# UVLO_MODULE_TOP.net
KiCad netlist of a schematic drawn in Altium Designer
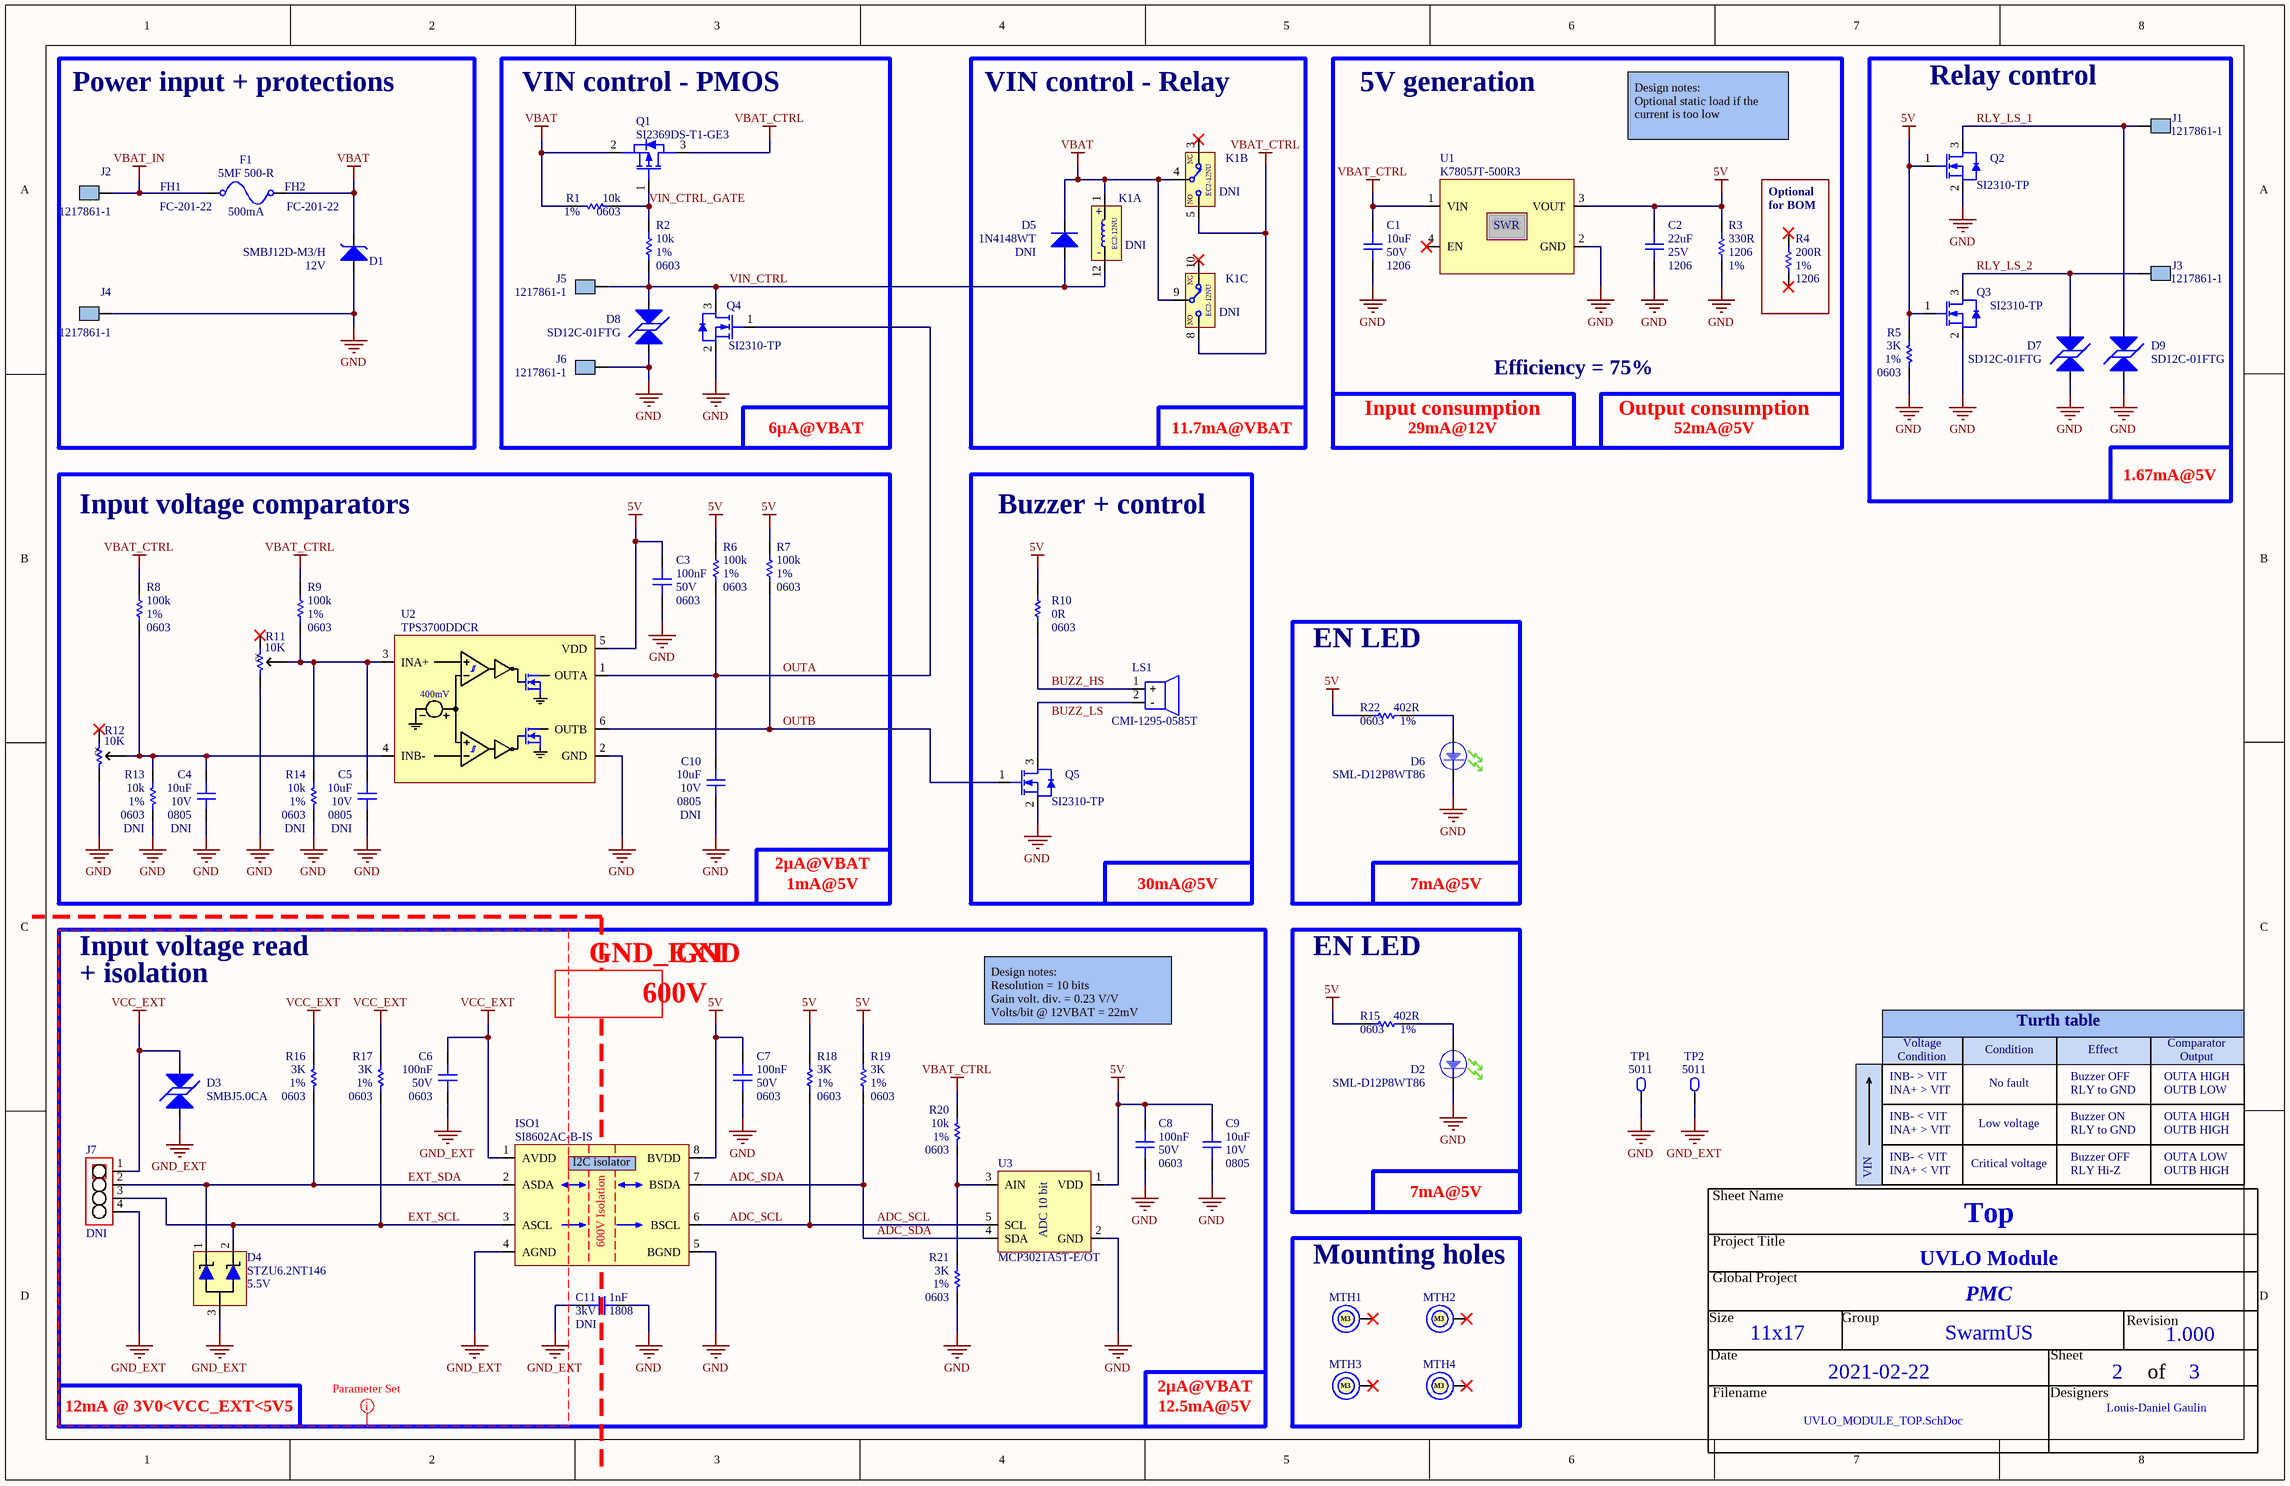
[diagram p0: UVLO_MODULE_TOP.SchDoc]

(export (version "E")
  (design (tool "Eeschema 10.0.6"))
  (components
    (comp (ref "C1")
      (value "10uF")
      (footprint "CAP_CER_1206")
      (description "CAP - CER 10UF 10% 50V X5R - 1206")
      (fields
        (field (name "TOLERANCE") "10%")
        (field (name "PACKAGE") "1206")
        (field (name "VOLTAGE RATING") "50V")
        (field (name "Comment") "GRT31CR61H106KE01L")
        (field (name "CREATEDBY/DATE") "Nicolas Roy - 2018/12/19")
        (field (name "VERIFIEDBY") "Nicolas V. (2019-01-22)")
      )
      (libsource (lib "GRAMS_MASTER_LIB") (part "CAP_CER_GRT31CR61H106KE01L"))
    )
    (comp (ref "C2")
      (value "22uF")
      (footprint "CAP_CER_1206")
      (description "CAP - CER 22uF 10% 25V X5R - 1206")
      (fields
        (field (name "TOLERANCE") "10%")
        (field (name "PACKAGE") "1206")
        (field (name "VOLTAGE RATING") "25V")
        (field (name "Comment") "CL31A226KAHNNNE")
        (field (name "CREATEDBY/DATE") "Philippe Arsenault/21 Janvier 2020")
        (field (name "VERIFIEDBY") "C.Paulin - 28/01/2020")
      )
      (libsource (lib "GRAMS_MASTER_LIB") (part "CAP_CER_CL31A226KAHNNNE"))
    )
    (comp (ref "C3")
      (value "100nF")
      (footprint "CAP_CER_0603")
      (description "CAP - CER 100nF 50V X7R - 0603")
      (fields
        (field (name "TOLERANCE") "10%")
        (field (name "PACKAGE") "0603")
        (field (name "VOLTAGE RATING") "50V")
        (field (name "Comment") "CC0603KRX7R9BB104")
        (field (name "CREATEDBY/DATE") "Louis-Daniel Gaulin / 25-02-2021")
        (field (name "VERIFIEDBY") "Hubert Dube - 26/02/2021")
      )
      (libsource (lib "SWARMUS_LIB") (part "CAP_CER_CC0603KRX7R9BB104"))
    )
    (comp (ref "C4")
      (value "10uF")
      (footprint "CAP_CER_0805")
      (description "CAP - CER 10UF 10% 10V X5R - 0805")
      (fields
        (field (name "TOLERANCE") "10%")
        (field (name "ASSEMBLY NOTE") "DNI")
        (field (name "PACKAGE") "0805")
        (field (name "VOLTAGE RATING") "10V")
        (field (name "Comment") "LMK212BJ106KG-T")
        (field (name "CREATEDBY/DATE") "Caroline Paulin / 25 juillet 2018")
        (field (name "VERIFIEDBY") "Nicolas V. (2019-01-22)")
      )
      (libsource (lib "GRAMS_MASTER_LIB") (part "CAP_CER_LMK212BJ106KG-T"))
    )
    (comp (ref "C5")
      (value "10uF")
      (footprint "CAP_CER_0805")
      (description "CAP - CER 10UF 10% 10V X5R - 0805")
      (fields
        (field (name "TOLERANCE") "10%")
        (field (name "ASSEMBLY NOTE") "DNI")
        (field (name "PACKAGE") "0805")
        (field (name "VOLTAGE RATING") "10V")
        (field (name "Comment") "LMK212BJ106KG-T")
        (field (name "CREATEDBY/DATE") "Caroline Paulin / 25 juillet 2018")
        (field (name "VERIFIEDBY") "Nicolas V. (2019-01-22)")
      )
      (libsource (lib "GRAMS_MASTER_LIB") (part "CAP_CER_LMK212BJ106KG-T"))
    )
    (comp (ref "C6")
      (value "100nF")
      (footprint "CAP_CER_0603")
      (description "CAP - CER 100nF 50V X7R - 0603")
      (fields
        (field (name "TOLERANCE") "10%")
        (field (name "PACKAGE") "0603")
        (field (name "VOLTAGE RATING") "50V")
        (field (name "Comment") "CC0603KRX7R9BB104")
        (field (name "CREATEDBY/DATE") "Louis-Daniel Gaulin / 25-02-2021")
        (field (name "VERIFIEDBY") "Hubert Dube - 26/02/2021")
      )
      (libsource (lib "SWARMUS_LIB") (part "CAP_CER_CC0603KRX7R9BB104"))
    )
    (comp (ref "C7")
      (value "100nF")
      (footprint "CAP_CER_0603")
      (description "CAP - CER 100nF 50V X7R - 0603")
      (fields
        (field (name "TOLERANCE") "10%")
        (field (name "PACKAGE") "0603")
        (field (name "VOLTAGE RATING") "50V")
        (field (name "Comment") "CC0603KRX7R9BB104")
        (field (name "CREATEDBY/DATE") "Louis-Daniel Gaulin / 25-02-2021")
        (field (name "VERIFIEDBY") "Hubert Dube - 26/02/2021")
      )
      (libsource (lib "SWARMUS_LIB") (part "CAP_CER_CC0603KRX7R9BB104"))
    )
    (comp (ref "C8")
      (value "100nF")
      (footprint "CAP_CER_0603")
      (description "CAP - CER 100nF 50V X7R - 0603")
      (fields
        (field (name "TOLERANCE") "10%")
        (field (name "PACKAGE") "0603")
        (field (name "VOLTAGE RATING") "50V")
        (field (name "Comment") "CC0603KRX7R9BB104")
        (field (name "CREATEDBY/DATE") "Louis-Daniel Gaulin / 25-02-2021")
        (field (name "VERIFIEDBY") "Hubert Dube - 26/02/2021")
      )
      (libsource (lib "SWARMUS_LIB") (part "CAP_CER_CC0603KRX7R9BB104"))
    )
    (comp (ref "C9")
      (value "10uF")
      (footprint "CAP_CER_0805")
      (description "CAP - CER 10UF 10% 10V X5R - 0805")
      (fields
        (field (name "TOLERANCE") "10%")
        (field (name "PACKAGE") "0805")
        (field (name "VOLTAGE RATING") "10V")
        (field (name "Comment") "LMK212BJ106KG-T")
        (field (name "CREATEDBY/DATE") "Caroline Paulin / 25 juillet 2018")
        (field (name "VERIFIEDBY") "Nicolas V. (2019-01-22)")
      )
      (libsource (lib "GRAMS_MASTER_LIB") (part "CAP_CER_LMK212BJ106KG-T"))
    )
    (comp (ref "C10")
      (value "10uF")
      (footprint "CAP_CER_0805")
      (description "CAP - CER 10UF 10% 10V X5R - 0805")
      (fields
        (field (name "TOLERANCE") "10%")
        (field (name "ASSEMBLY NOTE") "DNI")
        (field (name "PACKAGE") "0805")
        (field (name "VOLTAGE RATING") "10V")
        (field (name "Comment") "LMK212BJ106KG-T")
        (field (name "CREATEDBY/DATE") "Caroline Paulin / 25 juillet 2018")
        (field (name "VERIFIEDBY") "Nicolas V. (2019-01-22)")
      )
      (libsource (lib "GRAMS_MASTER_LIB") (part "CAP_CER_LMK212BJ106KG-T"))
    )
    (comp (ref "C11")
      (value "1nF")
      (footprint "CAP_CER_1808")
      (description "CAP - CER 1nF 10% 3kV X7R - 1808")
      (fields
        (field (name "TOLERANCE") "10%")
        (field (name "ASSEMBLY NOTE") "DNI")
        (field (name "PACKAGE") "1808")
        (field (name "VOLTAGE RATING") "3kV")
        (field (name "Comment") "1808HC102KAT1A")
        (field (name "CREATEDBY/DATE") "Joel Lemay 2018-08-29")
        (field (name "VERIFIEDBY") "Caroline Paulin - 7 sept 2018")
      )
      (libsource (lib "GRAMS_MASTER_LIB") (part "CAP_CER_1808HC102KAT1A"))
    )
    (comp (ref "D1")
      (value "SMBJ12D-M3/H")
      (footprint "TVS_SMBJ12D-M3/H")
      (description "TVS - DIODE 12V 19.6V - DO-214AA")
      (fields
        (field (name "ALTIUM_VALUE") "12V")
        (field (name "CREATEDBY/DATE") "Joel Lemay 2019-04-17")
        (field (name "VERIFIEDBY") "C.Paulin 6/02/2020")
      )
      (libsource (lib "GRAMS_MASTER_LIB") (part "TVS_SMBJ12D-M3/H"))
    )
    (comp (ref "D2")
      (value "SML-D12P8WT86")
      (footprint "LED_SML-D12P8WT86")
      (description "LED - GREEN DIFFUSED 0603 SMD - 0603")
      (fields
        (field (name "CREATEDBY/DATE") "Keven Deslandes - 2018/11/21")
        (field (name "VERIFIEDBY") "Caroline Paulin - 13 février 2019")
      )
      (libsource (lib "GRAMS_MASTER_LIB") (part "LED_SML-D12P8WT86"))
    )
    (comp (ref "D3")
      (value "SMBJ5.0CA")
      (footprint "TVS_PWR_SMBJ5.0CA")
      (description "TVS - BIDIR 5V 9.2V 600W - DO214AA")
      (fields
        (field (name "CREATEDBY/DATE") "Jonathan Bouchard - 2019-03-22")
        (field (name "VERIFIEDBY") "Nicolas V. (2019-05-06)")
      )
      (libsource (lib "GRAMS_MASTER_LIB") (part "TVS_PWR_SMBJ5.0CA"))
    )
    (comp (ref "D4")
      (value "STZU6.2NT146")
      (footprint "TVS_DATA_STZU6.2NT146")
      (description "TVS - TVS DIODE 5.5V 5.9V - SOT-23-3")
      (fields
        (field (name "VOLTAGE RATING") "5.5V")
        (field (name "CREATEDBY/DATE") "Louis-Daniel Gaulin / 02-03-2021")
        (field (name "VERIFIEDBY") "Philippe Arsenault / 02-03-2021")
      )
      (libsource (lib "SWARMUS_LIB") (part "TVS_DATA_STZU6.2NT146"))
    )
    (comp (ref "D5")
      (value "1N4148WT")
      (footprint "DIO_1N4148WT")
      (description "DIO - 1N4148WT - SOD-523F")
      (fields
        (field (name "ASSEMBLY NOTE") "DNI")
        (field (name "CREATEDBY/DATE") "Joel Lemay 2018-06-15")
        (field (name "VERIFIEDBY") "Arnaud Samson 17-07-18")
      )
      (libsource (lib "GRAMS_MASTER_LIB") (part "DIO_1N4148WT"))
    )
    (comp (ref "D6")
      (value "SML-D12P8WT86")
      (footprint "LED_SML-D12P8WT86")
      (description "LED - GREEN DIFFUSED 0603 SMD - 0603")
      (fields
        (field (name "CREATEDBY/DATE") "Keven Deslandes - 2018/11/21")
        (field (name "VERIFIEDBY") "Caroline Paulin - 13 février 2019")
      )
      (libsource (lib "GRAMS_MASTER_LIB") (part "LED_SML-D12P8WT86"))
    )
    (comp (ref "D7")
      (value "SD12C-01FTG")
      (footprint "TVS_DATA_SD12C-01FTG")
      (description "TVS - BIDIR 12V 450W - SOD-323")
      (fields
        (field (name "CREATEDBY/DATE") "O.D.Frenette - 2020-09-01")
        (field (name "VERIFIEDBY") "C.Paulin - 2020-09-09")
      )
      (libsource (lib "GRAMS_MASTER_LIB") (part "TVS_DATA_SD12C-01FTG"))
    )
    (comp (ref "D8")
      (value "SD12C-01FTG")
      (footprint "TVS_DATA_SD12C-01FTG")
      (description "TVS - BIDIR 12V 450W - SOD-323")
      (fields
        (field (name "CREATEDBY/DATE") "O.D.Frenette - 2020-09-01")
        (field (name "VERIFIEDBY") "C.Paulin - 2020-09-09")
      )
      (libsource (lib "GRAMS_MASTER_LIB") (part "TVS_DATA_SD12C-01FTG"))
    )
    (comp (ref "D9")
      (value "SD12C-01FTG")
      (footprint "TVS_DATA_SD12C-01FTG")
      (description "TVS - BIDIR 12V 450W - SOD-323")
      (fields
        (field (name "CREATEDBY/DATE") "O.D.Frenette - 2020-09-01")
        (field (name "VERIFIEDBY") "C.Paulin - 2020-09-09")
      )
      (libsource (lib "GRAMS_MASTER_LIB") (part "TVS_DATA_SD12C-01FTG"))
    )
    (comp (ref "F1")
      (value "5MF 500-R")
      (footprint "FUS_5MF 500-R")
      (description "FUS - CARTRIDGE GLASS 500mA 250VAC/125VDC - 5X20mm")
      (fields
        (field (name "CURRENT RATING") "500mA")
        (field (name "CREATEDBY/DATE") "Louis-Daniel Gaulin")
        (field (name "VERIFIEDBY") "Hubert Dube - 26/02/2021")
      )
      (libsource (lib "SWARMUS_LIB") (part "FUS_5MF 500-R"))
    )
    (comp (ref "FH1")
      (value "FC-201-22")
      (footprint "FHO_FC-201-22")
      (description "FHO - FUSE CLIP 5mm CARTRIDGE 10A PCB - 2-TH")
      (fields
        (field (name "CREATEDBY/DATE") "Louis-Daniel Gaulin / 26-02-2021")
        (field (name "VERIFIEDBY") "Hubert Dube - 26/02/2021")
      )
      (libsource (lib "SWARMUS_LIB") (part "FHO_FC-201-22"))
    )
    (comp (ref "FH2")
      (value "FC-201-22")
      (footprint "FHO_FC-201-22")
      (description "FHO - FUSE CLIP 5mm CARTRIDGE 10A PCB - 2-TH")
      (fields
        (field (name "CREATEDBY/DATE") "Louis-Daniel Gaulin / 26-02-2021")
        (field (name "VERIFIEDBY") "Hubert Dube - 26/02/2021")
      )
      (libsource (lib "SWARMUS_LIB") (part "FHO_FC-201-22"))
    )
    (comp (ref "ISO1")
      (value "SI8602AC-B-IS")
      (footprint "ISO_SI8602AC-B-IS")
      (description "ISO - DGTL ISO 600V 2CH I2C  - 8-SOIC")
      (fields
        (field (name "CREATEDBY/DATE") "Louis-Daniel Gaulin / 25-02-2021")
        (field (name "VERIFIEDBY") "Hubert Dube - 26/02/2021")
      )
      (libsource (lib "SWARMUS_LIB") (part "ISO_SI8602AC-B-IS"))
    )
    (comp (ref "J1")
      (value "1217861-1")
      (footprint "CON_1217861-1")
      (description "CON - Quick connect tab - TH")
      (fields
        (field (name "CREATEDBY/DATE") "Louis-Daniel Gaulin / 24-02-2021")
        (field (name "VERIFIEDBY") "Hubert Dube - 26/02/2021")
      )
      (libsource (lib "SWARMUS_LIB") (part "CON_1217861-1"))
    )
    (comp (ref "J2")
      (value "1217861-1")
      (footprint "CON_1217861-1")
      (description "CON - Quick connect tab - TH")
      (fields
        (field (name "CREATEDBY/DATE") "Louis-Daniel Gaulin / 24-02-2021")
        (field (name "VERIFIEDBY") "Hubert Dube - 26/02/2021")
      )
      (libsource (lib "") (part "CON_1217861-1_1"))
    )
    (comp (ref "J3")
      (value "1217861-1")
      (footprint "CON_1217861-1")
      (description "CON - Quick connect tab - TH")
      (fields
        (field (name "CREATEDBY/DATE") "Louis-Daniel Gaulin / 24-02-2021")
        (field (name "VERIFIEDBY") "Hubert Dube - 26/02/2021")
      )
      (libsource (lib "SWARMUS_LIB") (part "CON_1217861-1"))
    )
    (comp (ref "J4")
      (value "1217861-1")
      (footprint "CON_1217861-1")
      (description "CON - Quick connect tab - TH")
      (fields
        (field (name "CREATEDBY/DATE") "Louis-Daniel Gaulin / 24-02-2021")
        (field (name "VERIFIEDBY") "Hubert Dube - 26/02/2021")
      )
      (libsource (lib "") (part "CON_1217861-1_1"))
    )
    (comp (ref "J5")
      (value "1217861-1")
      (footprint "CON_1217861-1")
      (description "CON - Quick connect tab - TH")
      (fields
        (field (name "CREATEDBY/DATE") "Louis-Daniel Gaulin / 24-02-2021")
        (field (name "VERIFIEDBY") "Hubert Dube - 26/02/2021")
      )
      (libsource (lib "") (part "CON_1217861-1_1"))
    )
    (comp (ref "J6")
      (value "1217861-1")
      (footprint "CON_1217861-1")
      (description "CON - Quick connect tab - TH")
      (fields
        (field (name "CREATEDBY/DATE") "Louis-Daniel Gaulin / 24-02-2021")
        (field (name "VERIFIEDBY") "Hubert Dube - 26/02/2021")
      )
      (libsource (lib "") (part "CON_1217861-1_1"))
    )
    (comp (ref "J7")
      (value "CON_HDR_1X4")
      (footprint "CON_HDR_1X4")
      (description "CON - Header 1X4 pins, 100Mils - TH-4")
      (fields
        (field (name "ASSEMBLY NOTE") "DNI")
        (field (name "CREATEDBY/DATE") "Nicolas V (2020-02-24)")
        (field (name "VERIFIEDBY") "Nicolas V (2020-02-24)")
      )
      (libsource (lib "GRAMS_MASTER_LIB") (part "CON_HDR_1X4"))
    )
    (comp (ref "K1")
      (value "EC2-12NU")
      (footprint "RLY_EC2-12NU")
      (description "RLY - GENERAL PURPOSE DPDT 2A 12V - TH-8")
      (fields
        (field (name "ASSEMBLY NOTE") "DNI")
        (field (name "CREATEDBY/DATE") "Louis-Daniel Gaulin/02-03-2021")
        (field (name "VERIFIEDBY") "Philippe Arsenault/02-03-2021")
      )
      (libsource (lib "SWARMUS_LIB") (part "RLY_EC2-12NU"))
    )
    (comp (ref "LS1")
      (value "CMI-1295-0585T")
      (footprint "UND_SPK_CMI-1295-0585T")
      (description "LS - Buzzer indicator 5V 30mA 2.3kHz 85dB - TH")
      (fields
        (field (name "CREATEDBY/DATE") "Louis-Daniel Gaulin / 24-02-2021")
        (field (name "VERIFIEDBY") "Hubert Dube - 26/02/2021")
      )
      (libsource (lib "SWARMUS_LIB") (part "UND_LS_CMI-1295-0585T"))
    )
    (comp (ref "MTH1")
      (value "M3")
      (footprint "MTH_M3")
      (description "MTH - MOUNTING HOLE M3 PLATED - M3")
      (fields
        (field (name "CREATEDBY/DATE") "Jonathan Bouchard 2018-07-23")
        (field (name "VERIFIEDBY") "Arnaud Samson 23-07-18")
      )
      (libsource (lib "GRAMS_MASTER_LIB") (part "MTH_M3"))
    )
    (comp (ref "MTH2")
      (value "M3")
      (footprint "MTH_M3")
      (description "MTH - MOUNTING HOLE M3 PLATED - M3")
      (fields
        (field (name "CREATEDBY/DATE") "Jonathan Bouchard 2018-07-23")
        (field (name "VERIFIEDBY") "Arnaud Samson 23-07-18")
      )
      (libsource (lib "GRAMS_MASTER_LIB") (part "MTH_M3"))
    )
    (comp (ref "MTH3")
      (value "M3")
      (footprint "MTH_M3")
      (description "MTH - MOUNTING HOLE M3 PLATED - M3")
      (fields
        (field (name "CREATEDBY/DATE") "Jonathan Bouchard 2018-07-23")
        (field (name "VERIFIEDBY") "Arnaud Samson 23-07-18")
      )
      (libsource (lib "GRAMS_MASTER_LIB") (part "MTH_M3"))
    )
    (comp (ref "MTH4")
      (value "M3")
      (footprint "MTH_M3")
      (description "MTH - MOUNTING HOLE M3 PLATED - M3")
      (fields
        (field (name "CREATEDBY/DATE") "Jonathan Bouchard 2018-07-23")
        (field (name "VERIFIEDBY") "Arnaud Samson 23-07-18")
      )
      (libsource (lib "GRAMS_MASTER_LIB") (part "MTH_M3"))
    )
    (comp (ref "Q1")
      (value "SI2369DS-T1-GE3")
      (footprint "TRX_PMOS_SI2369DS-T1-GE3")
      (description "TRX - PMOS 30V 7.6A - SOT−23")
      (fields
        (field (name "CREATEDBY/DATE") "Louis-Daniel Gaulin / 30-07-2020")
        (field (name "VERIFIEDBY") "Philippe Arsenault/2020-11-06")
      )
      (libsource (lib "SWARMUS_LIB") (part "TRX_PMOS_SI2369DS-T1-GE3"))
    )
    (comp (ref "Q2")
      (value "SI2310-TP")
      (footprint "TRX_NMOS_SI2310-TP")
      (description "TRX - MOSFET N-CH 60V 3A - SOT-23")
      (fields
        (field (name "CREATEDBY/DATE") "Louis-Daniel Gaulin / 20-02-2020")
        (field (name "VERIFIEDBY") "C.Paulin - 21/02/2020")
      )
      (libsource (lib "GRAMS_MASTER_LIB") (part "TRX_NMOS_SI2310-TP"))
    )
    (comp (ref "Q3")
      (value "SI2310-TP")
      (footprint "TRX_NMOS_SI2310-TP")
      (description "TRX - MOSFET N-CH 60V 3A - SOT-23")
      (fields
        (field (name "CREATEDBY/DATE") "Louis-Daniel Gaulin / 20-02-2020")
        (field (name "VERIFIEDBY") "C.Paulin - 21/02/2020")
      )
      (libsource (lib "GRAMS_MASTER_LIB") (part "TRX_NMOS_SI2310-TP"))
    )
    (comp (ref "Q4")
      (value "SI2310-TP")
      (footprint "TRX_NMOS_SI2310-TP")
      (description "TRX - MOSFET N-CH 60V 3A - SOT-23")
      (fields
        (field (name "CREATEDBY/DATE") "Louis-Daniel Gaulin / 20-02-2020")
        (field (name "VERIFIEDBY") "C.Paulin - 21/02/2020")
      )
      (libsource (lib "GRAMS_MASTER_LIB") (part "TRX_NMOS_SI2310-TP"))
    )
    (comp (ref "Q5")
      (value "SI2310-TP")
      (footprint "TRX_NMOS_SI2310-TP")
      (description "TRX - MOSFET N-CH 60V 3A - SOT-23")
      (fields
        (field (name "CREATEDBY/DATE") "Louis-Daniel Gaulin / 20-02-2020")
        (field (name "VERIFIEDBY") "C.Paulin - 21/02/2020")
      )
      (libsource (lib "GRAMS_MASTER_LIB") (part "TRX_NMOS_SI2310-TP"))
    )
    (comp (ref "R1")
      (value "10k")
      (footprint "RES_0603")
      (description "RES - 10k 1% 1/10W - 0603")
      (fields
        (field (name "TOLERANCE") "1%")
        (field (name "PACKAGE") "0603")
        (field (name "Comment") "RC0603FR-0710KL")
        (field (name "CREATEDBY/DATE") "Louis-Daniel Gaulin / 24-02-2021")
        (field (name "VERIFIEDBY") "Hubert Dube - 26/02/2021")
      )
      (libsource (lib "SWARMUS_LIB") (part "RES_RC0603FR-0710KL"))
    )
    (comp (ref "R2")
      (value "10k")
      (footprint "RES_0603")
      (description "RES - 10k 1% 1/10W - 0603")
      (fields
        (field (name "TOLERANCE") "1%")
        (field (name "PACKAGE") "0603")
        (field (name "Comment") "RC0603FR-0710KL")
        (field (name "CREATEDBY/DATE") "Louis-Daniel Gaulin / 24-02-2021")
        (field (name "VERIFIEDBY") "Hubert Dube - 26/02/2021")
      )
      (libsource (lib "SWARMUS_LIB") (part "RES_RC0603FR-0710KL"))
    )
    (comp (ref "R3")
      (value "330R")
      (footprint "RES_1206")
      (description "RES - 330 OHM 1% 1/4W - 1206")
      (fields
        (field (name "TOLERANCE") "1%")
        (field (name "PACKAGE") "1206")
        (field (name "Comment") "RC1206FR-07330RL")
        (field (name "CREATEDBY/DATE") "Nicolas V. (2019-11-19)")
        (field (name "VERIFIEDBY") "Nicolas V. (2019-11-19)")
      )
      (libsource (lib "GRAMS_MASTER_LIB") (part "RES_RC1206FR-07330RL"))
    )
    (comp (ref "R4")
      (value "200R")
      (footprint "RES_1206")
      (description "RES - 200R 1% 1/4W - 1206")
      (fields
        (field (name "TOLERANCE") "1%")
        (field (name "PACKAGE") "1206")
        (field (name "Comment") "CRCW1206200RFKEAC")
        (field (name "CREATEDBY/DATE") "Louis-Daniel Gaulin / 26-02-2021")
        (field (name "VERIFIEDBY") "Hubert Dubé/ 26-02-2021")
      )
      (libsource (lib "SWARMUS_LIB") (part "RES_CRCW1206200RFKEAC"))
    )
    (comp (ref "R5")
      (value "3K")
      (footprint "RES_0603")
      (description "RES - 3k 1% 1/10W - 0603")
      (fields
        (field (name "TOLERANCE") "1%")
        (field (name "PACKAGE") "0603")
        (field (name "Comment") "RC0603FR-073KL")
        (field (name "CREATEDBY/DATE") "Louis-Daniel Gaulin / 24-02-2021")
        (field (name "VERIFIEDBY") "Hubert Dube - 26/02/2021")
      )
      (libsource (lib "SWARMUS_LIB") (part "RES_RC0603FR-073KL"))
    )
    (comp (ref "R6")
      (value "100k")
      (footprint "RES_0603")
      (description "RES - 100k 1% 1/10W - 0603")
      (fields
        (field (name "TOLERANCE") "1%")
        (field (name "PACKAGE") "0603")
        (field (name "Comment") "RC0603FR-07100KL")
        (field (name "CREATEDBY/DATE") "Louis-Daniel Gaulin / 24-02-2021")
        (field (name "VERIFIEDBY") "Hubert Dube")
      )
      (libsource (lib "SWARMUS_LIB") (part "RES_RC0603FR-07100KL"))
    )
    (comp (ref "R7")
      (value "100k")
      (footprint "RES_0603")
      (description "RES - 100k 1% 1/10W - 0603")
      (fields
        (field (name "TOLERANCE") "1%")
        (field (name "PACKAGE") "0603")
        (field (name "Comment") "RC0603FR-07100KL")
        (field (name "CREATEDBY/DATE") "Louis-Daniel Gaulin / 24-02-2021")
        (field (name "VERIFIEDBY") "Hubert Dube")
      )
      (libsource (lib "SWARMUS_LIB") (part "RES_RC0603FR-07100KL"))
    )
    (comp (ref "R8")
      (value "100k")
      (footprint "RES_0603")
      (description "RES - 100k 1% 1/10W - 0603")
      (fields
        (field (name "TOLERANCE") "1%")
        (field (name "PACKAGE") "0603")
        (field (name "Comment") "RC0603FR-07100KL")
        (field (name "CREATEDBY/DATE") "Louis-Daniel Gaulin / 24-02-2021")
        (field (name "VERIFIEDBY") "Hubert Dube")
      )
      (libsource (lib "SWARMUS_LIB") (part "RES_RC0603FR-07100KL"))
    )
    (comp (ref "R9")
      (value "100k")
      (footprint "RES_0603")
      (description "RES - 100k 1% 1/10W - 0603")
      (fields
        (field (name "TOLERANCE") "1%")
        (field (name "PACKAGE") "0603")
        (field (name "Comment") "RC0603FR-07100KL")
        (field (name "CREATEDBY/DATE") "Louis-Daniel Gaulin / 24-02-2021")
        (field (name "VERIFIEDBY") "Hubert Dube")
      )
      (libsource (lib "SWARMUS_LIB") (part "RES_RC0603FR-07100KL"))
    )
    (comp (ref "R10")
      (value "0R")
      (footprint "RES_0603")
      (description "RES - 0 ohm jumper 1/10W - 0603")
      (fields
        (field (name "PACKAGE") "0603")
        (field (name "Comment") "RC0603JR-070RL")
        (field (name "CREATEDBY/DATE") "L-P Gauthier 2018-10-30")
        (field (name "VERIFIEDBY") "Caroline Paulin  - 5/11/2018")
      )
      (libsource (lib "GRAMS_MASTER_LIB") (part "RES_RC0603JR-070RL"))
    )
    (comp (ref "R11")
      (value "10K")
      (footprint "POT_3362P-1-103LF")
      (description "RES -  POT 10K 1/2W LINEAR PLASTIC 1 turn - TH")
      (fields
        (field (name "TOLERANCE") "10%")
        (field (name "Comment") "3362P-1-103LF")
        (field (name "CREATEDBY/DATE") "Louis-Daniel Gaulin / 24-02-2021")
        (field (name "VERIFIEDBY") "Hubert Dube - 26/02/2021")
      )
      (libsource (lib "SWARMUS_LIB") (part "POT_3362P-1-103LF"))
    )
    (comp (ref "R12")
      (value "10K")
      (footprint "POT_3362P-1-103LF")
      (description "RES -  POT 10K 1/2W LINEAR PLASTIC 1 turn - TH")
      (fields
        (field (name "TOLERANCE") "10%")
        (field (name "Comment") "3362P-1-103LF")
        (field (name "CREATEDBY/DATE") "Louis-Daniel Gaulin / 24-02-2021")
        (field (name "VERIFIEDBY") "Hubert Dube - 26/02/2021")
      )
      (libsource (lib "SWARMUS_LIB") (part "POT_3362P-1-103LF"))
    )
    (comp (ref "R13")
      (value "10k")
      (footprint "RES_0603")
      (description "RES - 10k 1% 1/10W - 0603")
      (fields
        (field (name "ASSEMBLY NOTE") "DNI")
        (field (name "TOLERANCE") "1%")
        (field (name "PACKAGE") "0603")
        (field (name "Comment") "RC0603FR-0710KL")
        (field (name "CREATEDBY/DATE") "Louis-Daniel Gaulin / 24-02-2021")
        (field (name "VERIFIEDBY") "Hubert Dube - 26/02/2021")
      )
      (libsource (lib "SWARMUS_LIB") (part "RES_RC0603FR-0710KL"))
    )
    (comp (ref "R14")
      (value "10k")
      (footprint "RES_0603")
      (description "RES - 10k 1% 1/10W - 0603")
      (fields
        (field (name "ASSEMBLY NOTE") "DNI")
        (field (name "TOLERANCE") "1%")
        (field (name "PACKAGE") "0603")
        (field (name "Comment") "RC0603FR-0710KL")
        (field (name "CREATEDBY/DATE") "Louis-Daniel Gaulin / 24-02-2021")
        (field (name "VERIFIEDBY") "Hubert Dube - 26/02/2021")
      )
      (libsource (lib "SWARMUS_LIB") (part "RES_RC0603FR-0710KL"))
    )
    (comp (ref "R15")
      (value "402R")
      (footprint "RES_0603")
      (description "RES - 402R 1% 1/10W - 0603")
      (fields
        (field (name "TOLERANCE") "1%")
        (field (name "PACKAGE") "0603")
        (field (name "Comment") "RC0603FR-07402RL")
        (field (name "CREATEDBY/DATE") "Louis-Daniel Gaulin / 24-02-2021")
        (field (name "VERIFIEDBY") "Hubert Dube - 26/02/2021")
      )
      (libsource (lib "SWARMUS_LIB") (part "RES_RC0603FR-07402RL"))
    )
    (comp (ref "R16")
      (value "3K")
      (footprint "RES_0603")
      (description "RES - 3k 1% 1/10W - 0603")
      (fields
        (field (name "TOLERANCE") "1%")
        (field (name "PACKAGE") "0603")
        (field (name "Comment") "RC0603FR-073KL")
        (field (name "CREATEDBY/DATE") "Louis-Daniel Gaulin / 24-02-2021")
        (field (name "VERIFIEDBY") "Hubert Dube - 26/02/2021")
      )
      (libsource (lib "SWARMUS_LIB") (part "RES_RC0603FR-073KL"))
    )
    (comp (ref "R17")
      (value "3K")
      (footprint "RES_0603")
      (description "RES - 3k 1% 1/10W - 0603")
      (fields
        (field (name "TOLERANCE") "1%")
        (field (name "PACKAGE") "0603")
        (field (name "Comment") "RC0603FR-073KL")
        (field (name "CREATEDBY/DATE") "Louis-Daniel Gaulin / 24-02-2021")
        (field (name "VERIFIEDBY") "Hubert Dube - 26/02/2021")
      )
      (libsource (lib "SWARMUS_LIB") (part "RES_RC0603FR-073KL"))
    )
    (comp (ref "R18")
      (value "3K")
      (footprint "RES_0603")
      (description "RES - 3k 1% 1/10W - 0603")
      (fields
        (field (name "TOLERANCE") "1%")
        (field (name "PACKAGE") "0603")
        (field (name "Comment") "RC0603FR-073KL")
        (field (name "CREATEDBY/DATE") "Louis-Daniel Gaulin / 24-02-2021")
        (field (name "VERIFIEDBY") "Hubert Dube - 26/02/2021")
      )
      (libsource (lib "SWARMUS_LIB") (part "RES_RC0603FR-073KL"))
    )
    (comp (ref "R19")
      (value "3K")
      (footprint "RES_0603")
      (description "RES - 3k 1% 1/10W - 0603")
      (fields
        (field (name "TOLERANCE") "1%")
        (field (name "PACKAGE") "0603")
        (field (name "Comment") "RC0603FR-073KL")
        (field (name "CREATEDBY/DATE") "Louis-Daniel Gaulin / 24-02-2021")
        (field (name "VERIFIEDBY") "Hubert Dube - 26/02/2021")
      )
      (libsource (lib "SWARMUS_LIB") (part "RES_RC0603FR-073KL"))
    )
    (comp (ref "R20")
      (value "10k")
      (footprint "RES_0603")
      (description "RES - 10k 1% 1/10W - 0603")
      (fields
        (field (name "TOLERANCE") "1%")
        (field (name "PACKAGE") "0603")
        (field (name "Comment") "RC0603FR-0710KL")
        (field (name "CREATEDBY/DATE") "Louis-Daniel Gaulin / 24-02-2021")
        (field (name "VERIFIEDBY") "Hubert Dube - 26/02/2021")
      )
      (libsource (lib "SWARMUS_LIB") (part "RES_RC0603FR-0710KL"))
    )
    (comp (ref "R21")
      (value "3K")
      (footprint "RES_0603")
      (description "RES - 3k 1% 1/10W - 0603")
      (fields
        (field (name "TOLERANCE") "1%")
        (field (name "PACKAGE") "0603")
        (field (name "Comment") "RC0603FR-073KL")
        (field (name "CREATEDBY/DATE") "Louis-Daniel Gaulin / 24-02-2021")
        (field (name "VERIFIEDBY") "Hubert Dube - 26/02/2021")
      )
      (libsource (lib "SWARMUS_LIB") (part "RES_RC0603FR-073KL"))
    )
    (comp (ref "R22")
      (value "402R")
      (footprint "RES_0603")
      (description "RES - 402R 1% 1/10W - 0603")
      (fields
        (field (name "TOLERANCE") "1%")
        (field (name "PACKAGE") "0603")
        (field (name "Comment") "RC0603FR-07402RL")
        (field (name "CREATEDBY/DATE") "Louis-Daniel Gaulin / 24-02-2021")
        (field (name "VERIFIEDBY") "Hubert Dube - 26/02/2021")
      )
      (libsource (lib "SWARMUS_LIB") (part "RES_RC0603FR-07402RL"))
    )
    (comp (ref "TP1")
      (value "5011")
      (footprint "TPO_5011")
      (description "TPO - TEST POINT - TH")
      (fields
        (field (name "CREATEDBY/DATE") "Louis-Daniel Gauli / 02-11-2020")
        (field (name "VERIFIEDBY") "Philippe Arsenault/2020-11-06")
      )
      (libsource (lib "SWARMUS_LIB") (part "TPO_5011"))
    )
    (comp (ref "TP2")
      (value "5011")
      (footprint "TPO_5011")
      (description "TPO - TEST POINT - TH")
      (fields
        (field (name "CREATEDBY/DATE") "Louis-Daniel Gauli / 02-11-2020")
        (field (name "VERIFIEDBY") "Philippe Arsenault/2020-11-06")
      )
      (libsource (lib "SWARMUS_LIB") (part "TPO_5011"))
    )
    (comp (ref "U1")
      (value "K7805JT-500R3")
      (footprint "REG_SWR_K7805JT-500R3")
      (description "REG_DC DC CONVERTER 5V 2.5W - 4-SMD Module")
      (fields
        (field (name "CREATEDBY/DATE") "Louis-Daniel Gaulin / 25-02-2021")
        (field (name "VERIFIEDBY") "Hubert Dube - 26/02/2021")
      )
      (libsource (lib "SWARMUS_LIB") (part "REG_SWR_K7805JT-500R3"))
    )
    (comp (ref "U2")
      (value "TPS3700DDCR")
      (footprint "CMP_TPS3700DDCR")
      (description "CMP - Comparator Window Open Drain - TSOT-23-6")
      (fields
        (field (name "CREATEDBY/DATE") "Louis-Daniel Gaulin / 22-02-2021")
        (field (name "VERIFIEDBY") "Hubert Dube - 26/02/2021")
      )
      (libsource (lib "SWARMUS_LIB") (part "CMP_TPS3700DDCR"))
    )
    (comp (ref "U3")
      (value "MCP3021A5T-E/OT")
      (footprint "ADC_MCP3021A5T-E/OT")
      (description "ADC - IC ADC 10BIT I2C 22.3KSPS - SOT-23-5")
      (fields
        (field (name "CREATEDBY/DATE") "Louis-Daniel Gaulin / 24-02-2021")
        (field (name "VERIFIEDBY") "Hubert Dube - 26/02/2021")
      )
      (libsource (lib "SWARMUS_LIB") (part "ADC_MCP3021A5T-E/OT"))
    )
  )
  (nets
    (net (code "1") (name "/ADC_SCL") (class "Default")
      (node (ref "ISO1") (pin "6") (pinfunction "BSCL_6") (pintype "passive"))
      (node (ref "R18") (pin "1") (pinfunction "1_1") (pintype "passive"))
      (node (ref "U3") (pin "5") (pinfunction "SCL_5") (pintype "passive"))
    )
    (net (code "2") (name "/ADC_SDA") (class "Default")
      (node (ref "ISO1") (pin "7") (pinfunction "BSDA_7") (pintype "passive"))
      (node (ref "R19") (pin "1") (pinfunction "1_1") (pintype "passive"))
      (node (ref "U3") (pin "4") (pinfunction "SDA_4") (pintype "passive"))
    )
    (net (code "3") (name "/BUZZ_HS") (class "Default")
      (node (ref "LS1") (pin "1") (pinfunction "+_1") (pintype "passive"))
      (node (ref "R10") (pin "1") (pinfunction "1_1") (pintype "passive"))
    )
    (net (code "4") (name "/BUZZ_LS") (class "Default")
      (node (ref "LS1") (pin "2") (pinfunction "-_2") (pintype "passive"))
      (node (ref "Q5") (pin "3") (pinfunction "D_3") (pintype "passive"))
    )
    (net (code "5") (name "/EXT_SCL") (class "Default")
      (node (ref "D4") (pin "2") (pinfunction "K2_2") (pintype "passive"))
      (node (ref "ISO1") (pin "3") (pinfunction "ASCL_3") (pintype "passive"))
      (node (ref "J7") (pin "3") (pinfunction "3_3") (pintype "passive"))
      (node (ref "R17") (pin "1") (pinfunction "1_1") (pintype "passive"))
    )
    (net (code "6") (name "/EXT_SDA") (class "Default")
      (node (ref "D4") (pin "1") (pinfunction "K1_1") (pintype "passive"))
      (node (ref "ISO1") (pin "2") (pinfunction "ASDA_2") (pintype "passive"))
      (node (ref "J7") (pin "2") (pinfunction "2_2") (pintype "passive"))
      (node (ref "R16") (pin "1") (pinfunction "1_1") (pintype "passive"))
    )
    (net (code "7") (name "/OUTA") (class "Default")
      (node (ref "C10") (pin "2") (pinfunction "2_2") (pintype "passive"))
      (node (ref "Q4") (pin "1") (pinfunction "G_1") (pintype "passive"))
      (node (ref "R6") (pin "1") (pinfunction "1_1") (pintype "passive"))
      (node (ref "U2") (pin "1") (pinfunction "OUTA_1") (pintype "passive"))
    )
    (net (code "8") (name "/OUTB") (class "Default")
      (node (ref "Q5") (pin "1") (pinfunction "G_1") (pintype "passive"))
      (node (ref "R7") (pin "1") (pinfunction "1_1") (pintype "passive"))
      (node (ref "U2") (pin "6") (pinfunction "OUTB_6") (pintype "passive"))
    )
    (net (code "9") (name "/RLY_LS_1") (class "Default")
      (node (ref "D9") (pin "1") (pinfunction "1_1") (pintype "passive"))
      (node (ref "J1") (pin "1") (pintype "passive"))
      (node (ref "Q2") (pin "3") (pinfunction "D_3") (pintype "passive"))
    )
    (net (code "10") (name "/RLY_LS_2") (class "Default")
      (node (ref "D7") (pin "1") (pinfunction "1_1") (pintype "passive"))
      (node (ref "J3") (pin "1") (pintype "passive"))
      (node (ref "Q3") (pin "3") (pinfunction "D_3") (pintype "passive"))
    )
    (net (code "11") (name "/VIN_CTRL") (class "Default")
      (node (ref "D5") (pin "A") (pinfunction "A_A") (pintype "passive"))
      (node (ref "D8") (pin "1") (pinfunction "1_1") (pintype "passive"))
      (node (ref "J5") (pin "1") (pintype "passive"))
      (node (ref "K1") (pin "12") (pinfunction "COIL-_12") (pintype "passive"))
      (node (ref "Q4") (pin "3") (pinfunction "D_3") (pintype "passive"))
      (node (ref "R2") (pin "1") (pinfunction "1_1") (pintype "passive"))
    )
    (net (code "12") (name "/VIN_CTRL_GATE") (class "Default")
      (node (ref "Q1") (pin "1") (pinfunction "G_1") (pintype "passive"))
      (node (ref "R1") (pin "1") (pinfunction "1_1") (pintype "passive"))
      (node (ref "R2") (pin "2") (pinfunction "2_2") (pintype "passive"))
    )
    (net (code "13") (name "5V") (class "Default")
      (node (ref "C2") (pin "2") (pinfunction "2_2") (pintype "passive"))
      (node (ref "C3") (pin "2") (pinfunction "2_2") (pintype "passive"))
      (node (ref "C7") (pin "2") (pinfunction "2_2") (pintype "passive"))
      (node (ref "C8") (pin "2") (pinfunction "2_2") (pintype "passive"))
      (node (ref "C9") (pin "2") (pinfunction "2_2") (pintype "passive"))
      (node (ref "ISO1") (pin "8") (pinfunction "BVDD_8") (pintype "passive"))
      (node (ref "Q2") (pin "1") (pinfunction "G_1") (pintype "passive"))
      (node (ref "Q3") (pin "1") (pinfunction "G_1") (pintype "passive"))
      (node (ref "R10") (pin "2") (pinfunction "2_2") (pintype "passive"))
      (node (ref "R15") (pin "1") (pinfunction "1_1") (pintype "passive"))
      (node (ref "R18") (pin "2") (pinfunction "2_2") (pintype "passive"))
      (node (ref "R19") (pin "2") (pinfunction "2_2") (pintype "passive"))
      (node (ref "R22") (pin "1") (pinfunction "1_1") (pintype "passive"))
      (node (ref "R3") (pin "2") (pinfunction "2_2") (pintype "passive"))
      (node (ref "R5") (pin "2") (pinfunction "2_2") (pintype "passive"))
      (node (ref "R6") (pin "2") (pinfunction "2_2") (pintype "passive"))
      (node (ref "R7") (pin "2") (pinfunction "2_2") (pintype "passive"))
      (node (ref "U1") (pin "3") (pinfunction "VOUT_3") (pintype "passive"))
      (node (ref "U2") (pin "5") (pinfunction "VDD_5") (pintype "passive"))
      (node (ref "U3") (pin "1") (pinfunction "VDD_1") (pintype "passive"))
    )
    (net (code "14") (name "GND") (class "Default")
      (node (ref "C1") (pin "1") (pinfunction "1_1") (pintype "passive"))
      (node (ref "C10") (pin "1") (pinfunction "1_1") (pintype "passive"))
      (node (ref "C11") (pin "1") (pinfunction "1_1") (pintype "passive"))
      (node (ref "C2") (pin "1") (pinfunction "1_1") (pintype "passive"))
      (node (ref "C3") (pin "1") (pinfunction "1_1") (pintype "passive"))
      (node (ref "C4") (pin "1") (pinfunction "1_1") (pintype "passive"))
      (node (ref "C5") (pin "1") (pinfunction "1_1") (pintype "passive"))
      (node (ref "C7") (pin "1") (pinfunction "1_1") (pintype "passive"))
      (node (ref "C8") (pin "1") (pinfunction "1_1") (pintype "passive"))
      (node (ref "C9") (pin "1") (pinfunction "1_1") (pintype "passive"))
      (node (ref "D1") (pin "1") (pinfunction "A_1") (pintype "passive"))
      (node (ref "D2") (pin "K") (pinfunction "K_K") (pintype "passive"))
      (node (ref "D6") (pin "K") (pinfunction "K_K") (pintype "passive"))
      (node (ref "D7") (pin "2") (pinfunction "2_2") (pintype "passive"))
      (node (ref "D8") (pin "2") (pinfunction "2_2") (pintype "passive"))
      (node (ref "D9") (pin "2") (pinfunction "2_2") (pintype "passive"))
      (node (ref "ISO1") (pin "5") (pinfunction "BGND_5") (pintype "passive"))
      (node (ref "J4") (pin "1") (pintype "passive"))
      (node (ref "J6") (pin "1") (pintype "passive"))
      (node (ref "Q2") (pin "2") (pinfunction "S_2") (pintype "passive"))
      (node (ref "Q3") (pin "2") (pinfunction "S_2") (pintype "passive"))
      (node (ref "Q4") (pin "2") (pinfunction "S_2") (pintype "passive"))
      (node (ref "Q5") (pin "2") (pinfunction "S_2") (pintype "passive"))
      (node (ref "R11") (pin "1") (pinfunction "1_1") (pintype "passive"))
      (node (ref "R12") (pin "1") (pinfunction "1_1") (pintype "passive"))
      (node (ref "R13") (pin "1") (pinfunction "1_1") (pintype "passive"))
      (node (ref "R14") (pin "1") (pinfunction "1_1") (pintype "passive"))
      (node (ref "R21") (pin "1") (pinfunction "1_1") (pintype "passive"))
      (node (ref "R3") (pin "1") (pinfunction "1_1") (pintype "passive"))
      (node (ref "R5") (pin "1") (pinfunction "1_1") (pintype "passive"))
      (node (ref "TP1") (pin "1") (pinfunction "1_1") (pintype "passive"))
      (node (ref "U1") (pin "2") (pinfunction "GND_2") (pintype "passive"))
      (node (ref "U2") (pin "2") (pinfunction "GND_2") (pintype "passive"))
      (node (ref "U3") (pin "2") (pinfunction "GND_2") (pintype "passive"))
    )
    (net (code "15") (name "GND_EXT") (class "Default")
      (node (ref "C11") (pin "2") (pinfunction "2_2") (pintype "passive"))
      (node (ref "C6") (pin "1") (pinfunction "1_1") (pintype "passive"))
      (node (ref "D3") (pin "2") (pinfunction "2_2") (pintype "passive"))
      (node (ref "D4") (pin "3") (pinfunction "A_3") (pintype "passive"))
      (node (ref "ISO1") (pin "4") (pinfunction "AGND_4") (pintype "passive"))
      (node (ref "J7") (pin "4") (pinfunction "4_4") (pintype "passive"))
      (node (ref "TP2") (pin "1") (pinfunction "1_1") (pintype "passive"))
    )
    (net (code "16") (name "Net-(D2-PadA)") (class "Default")
      (node (ref "D2") (pin "A") (pinfunction "A_A") (pintype "passive"))
      (node (ref "R15") (pin "2") (pinfunction "2_2") (pintype "passive"))
    )
    (net (code "17") (name "Net-(D6-PadA)") (class "Default")
      (node (ref "D6") (pin "A") (pinfunction "A_A") (pintype "passive"))
      (node (ref "R22") (pin "2") (pinfunction "2_2") (pintype "passive"))
    )
    (net (code "18") (name "Net-(U2-INA+)") (class "Default")
      (node (ref "C5") (pin "2") (pinfunction "2_2") (pintype "passive"))
      (node (ref "R11") (pin "2") (pinfunction "2_2") (pintype "passive"))
      (node (ref "R14") (pin "2") (pinfunction "2_2") (pintype "passive"))
      (node (ref "R9") (pin "1") (pinfunction "1_1") (pintype "passive"))
      (node (ref "U2") (pin "3") (pinfunction "INA+_3") (pintype "passive"))
    )
    (net (code "19") (name "Net-(U2-INB-)") (class "Default")
      (node (ref "C4") (pin "2") (pinfunction "2_2") (pintype "passive"))
      (node (ref "R12") (pin "2") (pinfunction "2_2") (pintype "passive"))
      (node (ref "R13") (pin "2") (pinfunction "2_2") (pintype "passive"))
      (node (ref "R8") (pin "1") (pinfunction "1_1") (pintype "passive"))
      (node (ref "U2") (pin "4") (pinfunction "INB-_4") (pintype "passive"))
    )
    (net (code "20") (name "Net-(U3-AIN)") (class "Default")
      (node (ref "R20") (pin "1") (pinfunction "1_1") (pintype "passive"))
      (node (ref "R21") (pin "2") (pinfunction "2_2") (pintype "passive"))
      (node (ref "U3") (pin "3") (pinfunction "AIN_3") (pintype "passive"))
    )
    (net (code "21") (name "VBAT") (class "Default")
      (node (ref "D1") (pin "2") (pinfunction "K_2") (pintype "passive"))
      (node (ref "D5") (pin "K") (pinfunction "K_K") (pintype "passive"))
      (node (ref "FH2") (pin "1") (pinfunction "1_1") (pintype "passive"))
      (node (ref "K1") (pin "1") (pinfunction "COIL+_1") (pintype "passive"))
      (node (ref "K1") (pin "4") (pinfunction "COM1_4") (pintype "passive"))
      (node (ref "K1") (pin "9") (pinfunction "COM2_9") (pintype "passive"))
      (node (ref "Q1") (pin "2") (pinfunction "S_2") (pintype "passive"))
      (node (ref "R1") (pin "2") (pinfunction "2_2") (pintype "passive"))
    )
    (net (code "22") (name "VBAT_CTRL") (class "Default")
      (node (ref "C1") (pin "2") (pinfunction "2_2") (pintype "passive"))
      (node (ref "K1") (pin "5") (pinfunction "NO1_5") (pintype "passive"))
      (node (ref "K1") (pin "8") (pinfunction "NO2_8") (pintype "passive"))
      (node (ref "Q1") (pin "3") (pinfunction "D_3") (pintype "passive"))
      (node (ref "R20") (pin "2") (pinfunction "2_2") (pintype "passive"))
      (node (ref "R8") (pin "2") (pinfunction "2_2") (pintype "passive"))
      (node (ref "R9") (pin "2") (pinfunction "2_2") (pintype "passive"))
      (node (ref "U1") (pin "1") (pinfunction "VIN_1") (pintype "passive"))
    )
    (net (code "23") (name "VBAT_IN") (class "Default")
      (node (ref "FH1") (pin "1") (pinfunction "1_1") (pintype "passive"))
      (node (ref "J2") (pin "1") (pintype "passive"))
    )
    (net (code "24") (name "VCC_EXT") (class "Default")
      (node (ref "C6") (pin "2") (pinfunction "2_2") (pintype "passive"))
      (node (ref "D3") (pin "1") (pinfunction "1_1") (pintype "passive"))
      (node (ref "ISO1") (pin "1") (pinfunction "AVDD_1") (pintype "passive"))
      (node (ref "J7") (pin "1") (pinfunction "1_1") (pintype "passive"))
      (node (ref "R16") (pin "2") (pinfunction "2_2") (pintype "passive"))
      (node (ref "R17") (pin "2") (pinfunction "2_2") (pintype "passive"))
    )
    (net (code "25") (name "unconnected-(K1B-NC1-Pad3)") (class "Default")
      (node (ref "K1") (pin "3") (pinfunction "NC1_3") (pintype "passive+no_connect"))
    )
    (net (code "26") (name "unconnected-(K1C-NC2-Pad10)") (class "Default")
      (node (ref "K1") (pin "10") (pinfunction "NC2_10") (pintype "passive+no_connect"))
    )
    (net (code "27") (name "unconnected-(MTH1-Pad1)") (class "Default")
      (node (ref "MTH1") (pin "1") (pinfunction "1_1") (pintype "passive+no_connect"))
    )
    (net (code "28") (name "unconnected-(MTH2-Pad1)") (class "Default")
      (node (ref "MTH2") (pin "1") (pinfunction "1_1") (pintype "passive+no_connect"))
    )
    (net (code "29") (name "unconnected-(MTH3-Pad1)") (class "Default")
      (node (ref "MTH3") (pin "1") (pinfunction "1_1") (pintype "passive+no_connect"))
    )
    (net (code "30") (name "unconnected-(MTH4-Pad1)") (class "Default")
      (node (ref "MTH4") (pin "1") (pinfunction "1_1") (pintype "passive+no_connect"))
    )
    (net (code "31") (name "unconnected-(R4-Pad1)") (class "Default")
      (node (ref "R4") (pin "1") (pinfunction "1_1") (pintype "passive+no_connect"))
    )
    (net (code "32") (name "unconnected-(R4-Pad2)") (class "Default")
      (node (ref "R4") (pin "2") (pinfunction "2_2") (pintype "passive+no_connect"))
    )
    (net (code "33") (name "unconnected-(R11-Pad3)") (class "Default")
      (node (ref "R11") (pin "3") (pinfunction "3_3") (pintype "passive+no_connect"))
    )
    (net (code "34") (name "unconnected-(R12-Pad3)") (class "Default")
      (node (ref "R12") (pin "3") (pinfunction "3_3") (pintype "passive+no_connect"))
    )
    (net (code "35") (name "unconnected-(U1-EN-Pad4)") (class "Default")
      (node (ref "U1") (pin "4") (pinfunction "EN_4") (pintype "passive+no_connect"))
    )
  )
)
